# MON-PCP-2-2.net
KiCad netlist of a schematic drawn in EAGLE
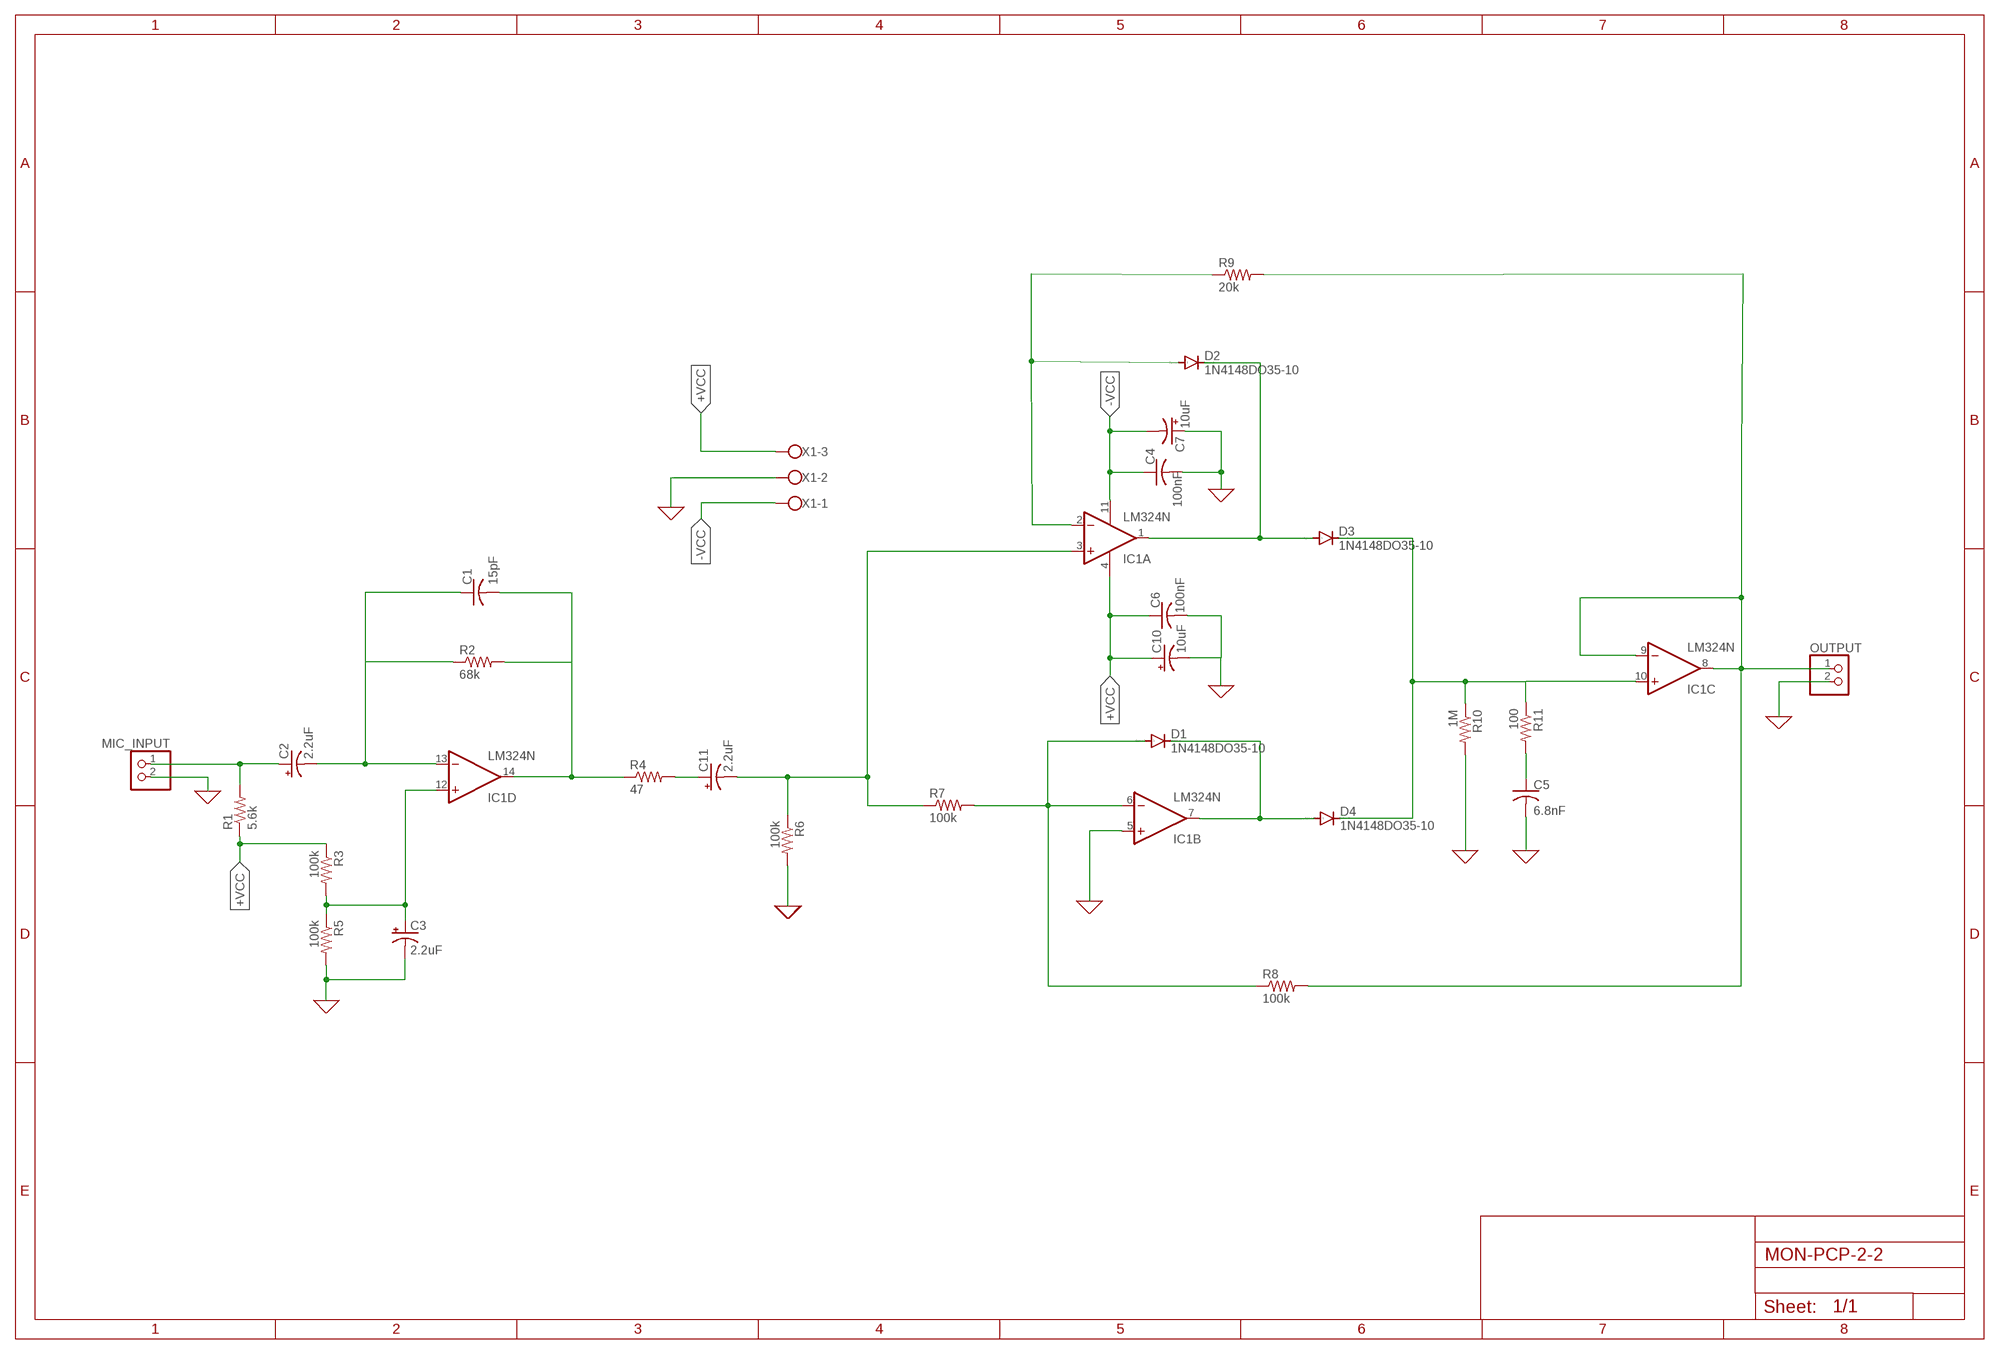
[diagram p0: schematic, sheet 1]

(export (version "E")
  (design (tool "Eeschema 10.0.6"))
  (components
    (comp (ref "C1")
      (value "15pF")
      (footprint "eagle-import:C050-025X075")
      (libsource (lib "eagle-import") (part "C-US050-025X075"))
    )
    (comp (ref "C2")
      (value "2.2uF")
      (footprint "eagle-import:E2,5-7")
      (libsource (lib "eagle-import") (part "CPOL-USE2.5-7"))
    )
    (comp (ref "C3")
      (value "2.2uF")
      (footprint "eagle-import:E2,5-7")
      (libsource (lib "eagle-import") (part "CPOL-USE2.5-7"))
    )
    (comp (ref "C4")
      (value "100nF")
      (footprint "eagle-import:C050-025X075")
      (libsource (lib "eagle-import") (part "C-US050-025X075"))
    )
    (comp (ref "C5")
      (value "6.8nF")
      (footprint "eagle-import:C050-025X075")
      (libsource (lib "eagle-import") (part "C-US050-025X075"))
    )
    (comp (ref "C6")
      (value "100nF")
      (footprint "eagle-import:C050-025X075")
      (libsource (lib "eagle-import") (part "C-US050-025X075"))
    )
    (comp (ref "C7")
      (value "10uF")
      (footprint "eagle-import:E2,5-7")
      (libsource (lib "eagle-import") (part "CPOL-USE2.5-7"))
    )
    (comp (ref "C10")
      (value "10uF")
      (footprint "eagle-import:E2,5-7")
      (libsource (lib "eagle-import") (part "CPOL-USE2.5-7"))
    )
    (comp (ref "C11")
      (value "2.2uF")
      (footprint "eagle-import:E2,5-7")
      (libsource (lib "eagle-import") (part "CPOL-USE2.5-7"))
    )
    (comp (ref "D1")
      (value "1N4148DO35-10")
      (footprint "eagle-import:DO35-10")
      (libsource (lib "eagle-import") (part "1N4148DO35-10"))
    )
    (comp (ref "D2")
      (value "1N4148DO35-10")
      (footprint "eagle-import:DO35-10")
      (libsource (lib "eagle-import") (part "1N4148DO35-10"))
    )
    (comp (ref "D3")
      (value "1N4148DO35-10")
      (footprint "eagle-import:DO35-10")
      (libsource (lib "eagle-import") (part "1N4148DO35-10"))
    )
    (comp (ref "D4")
      (value "1N4148DO35-10")
      (footprint "eagle-import:DO35-10")
      (libsource (lib "eagle-import") (part "1N4148DO35-10"))
    )
    (comp (ref "IC1")
      (value "LM324N")
      (footprint "eagle-import:DIL14")
      (libsource (lib "eagle-import") (part "LM324N"))
    )
    (comp (ref "MIC_INPUT")
      (value "PINHD-1X2")
      (footprint "eagle-import:1X02")
      (libsource (lib "eagle-import") (part "PINHD-1X2"))
    )
    (comp (ref "OUTPUT")
      (value "PINHD-1X2")
      (footprint "eagle-import:1X02")
      (libsource (lib "eagle-import") (part "PINHD-1X2"))
    )
    (comp (ref "R1")
      (value "5.6k")
      (footprint "eagle-import:0207_10")
      (libsource (lib "eagle-import") (part "R-US_0207/10"))
    )
    (comp (ref "R2")
      (value "68k")
      (footprint "eagle-import:0207_10")
      (libsource (lib "eagle-import") (part "R-US_0207/10"))
    )
    (comp (ref "R3")
      (value "100k")
      (footprint "eagle-import:0207_10")
      (libsource (lib "eagle-import") (part "R-US_0207/10"))
    )
    (comp (ref "R4")
      (value "47")
      (footprint "eagle-import:0207_10")
      (libsource (lib "eagle-import") (part "R-US_0207/10"))
    )
    (comp (ref "R5")
      (value "100k")
      (footprint "eagle-import:0207_10")
      (libsource (lib "eagle-import") (part "R-US_0207/10"))
    )
    (comp (ref "R6")
      (value "100k")
      (footprint "eagle-import:0207_10")
      (libsource (lib "eagle-import") (part "R-US_0207/10"))
    )
    (comp (ref "R7")
      (value "100k")
      (footprint "eagle-import:0207_10")
      (libsource (lib "eagle-import") (part "R-US_0207/10"))
    )
    (comp (ref "R8")
      (value "100k")
      (footprint "eagle-import:0207_10")
      (libsource (lib "eagle-import") (part "R-US_0207/10"))
    )
    (comp (ref "R9")
      (value "20k")
      (footprint "eagle-import:0207_10")
      (libsource (lib "eagle-import") (part "R-US_0207/10"))
    )
    (comp (ref "R10")
      (value "1M")
      (footprint "eagle-import:0207_10")
      (libsource (lib "eagle-import") (part "R-US_0207/10"))
    )
    (comp (ref "R11")
      (value "100")
      (footprint "eagle-import:0207_10")
      (libsource (lib "eagle-import") (part "R-US_0207/10"))
    )
    (comp (ref "X1")
      (value "W237-103")
      (footprint "eagle-import:W237-103")
      (fields (field (name "MPN") "237-103"))
      (libsource (lib "eagle-import") (part "W237-103"))
    )
  )
  (nets
    (net (code "1") (name "+VCC") (class "Default")
      (node (ref "C10") (pin "+") (pinfunction "+_+") (pintype "passive"))
      (node (ref "C6") (pin "1") (pinfunction "1_1") (pintype "passive"))
      (node (ref "IC1") (pin "4") (pinfunction "V+_4") (pintype "power_in"))
      (node (ref "R1") (pin "1") (pinfunction "1_1") (pintype "passive"))
      (node (ref "R3") (pin "1") (pinfunction "1_1") (pintype "passive"))
      (node (ref "X1") (pin "3") (pinfunction "KL_3") (pintype "passive"))
    )
    (net (code "2") (name "-VCC") (class "Default")
      (node (ref "C4") (pin "1") (pinfunction "1_1") (pintype "passive"))
      (node (ref "C7") (pin "-") (pinfunction "-_-") (pintype "passive"))
      (node (ref "IC1") (pin "11") (pinfunction "V-_11") (pintype "power_in"))
      (node (ref "X1") (pin "1") (pinfunction "KL_1") (pintype "passive"))
    )
    (net (code "3") (name "GND") (class "Default")
      (node (ref "C10") (pin "-") (pinfunction "-_-") (pintype "passive"))
      (node (ref "C3") (pin "-") (pinfunction "-_-") (pintype "passive"))
      (node (ref "C4") (pin "2") (pinfunction "2_2") (pintype "passive"))
      (node (ref "C5") (pin "2") (pinfunction "2_2") (pintype "passive"))
      (node (ref "C6") (pin "2") (pinfunction "2_2") (pintype "passive"))
      (node (ref "C7") (pin "+") (pinfunction "+_+") (pintype "passive"))
      (node (ref "IC1") (pin "5") (pinfunction "+IN_5") (pintype "input"))
      (node (ref "MIC_INPUT") (pin "2") (pinfunction "2_2") (pintype "passive"))
      (node (ref "OUTPUT") (pin "2") (pinfunction "2_2") (pintype "passive"))
      (node (ref "R10") (pin "2") (pinfunction "2_2") (pintype "passive"))
      (node (ref "R5") (pin "2") (pinfunction "2_2") (pintype "passive"))
      (node (ref "R6") (pin "2") (pinfunction "2_2") (pintype "passive"))
      (node (ref "X1") (pin "2") (pinfunction "KL_2") (pintype "passive"))
    )
    (net (code "4") (name "Net-(C2-Pad+)") (class "Default")
      (node (ref "C2") (pin "+") (pinfunction "+_+") (pintype "passive"))
      (node (ref "MIC_INPUT") (pin "1") (pinfunction "1_1") (pintype "passive"))
      (node (ref "R1") (pin "2") (pinfunction "2_2") (pintype "passive"))
    )
    (net (code "5") (name "Net-(C5-Pad1)") (class "Default")
      (node (ref "C5") (pin "1") (pinfunction "1_1") (pintype "passive"))
      (node (ref "R11") (pin "2") (pinfunction "2_2") (pintype "passive"))
    )
    (net (code "6") (name "Net-(C11-Pad+)") (class "Default")
      (node (ref "C11") (pin "+") (pinfunction "+_+") (pintype "passive"))
      (node (ref "R4") (pin "2") (pinfunction "2_2") (pintype "passive"))
    )
    (net (code "7") (name "Net-(IC1A-+IN)") (class "Default")
      (node (ref "C11") (pin "-") (pinfunction "-_-") (pintype "passive"))
      (node (ref "IC1") (pin "3") (pinfunction "+IN_3") (pintype "input"))
      (node (ref "R6") (pin "1") (pinfunction "1_1") (pintype "passive"))
      (node (ref "R7") (pin "1") (pinfunction "1_1") (pintype "passive"))
    )
    (net (code "8") (name "Net-(IC1A--IN)") (class "Default")
      (node (ref "D2") (pin "A") (pinfunction "A_A") (pintype "passive"))
      (node (ref "IC1") (pin "2") (pinfunction "-IN_2") (pintype "input"))
      (node (ref "R9") (pin "1") (pinfunction "1_1") (pintype "passive"))
    )
    (net (code "9") (name "Net-(IC1A-OUT)") (class "Default")
      (node (ref "D2") (pin "C") (pinfunction "C_C") (pintype "passive"))
      (node (ref "D3") (pin "A") (pinfunction "A_A") (pintype "passive"))
      (node (ref "IC1") (pin "1") (pinfunction "OUT_1") (pintype "output"))
    )
    (net (code "10") (name "Net-(IC1B--IN)") (class "Default")
      (node (ref "D1") (pin "A") (pinfunction "A_A") (pintype "passive"))
      (node (ref "IC1") (pin "6") (pinfunction "-IN_6") (pintype "input"))
      (node (ref "R7") (pin "2") (pinfunction "2_2") (pintype "passive"))
      (node (ref "R8") (pin "1") (pinfunction "1_1") (pintype "passive"))
    )
    (net (code "11") (name "Net-(IC1B-OUT)") (class "Default")
      (node (ref "D1") (pin "C") (pinfunction "C_C") (pintype "passive"))
      (node (ref "D4") (pin "A") (pinfunction "A_A") (pintype "passive"))
      (node (ref "IC1") (pin "7") (pinfunction "OUT_7") (pintype "output"))
    )
    (net (code "12") (name "Net-(IC1C-+IN)") (class "Default")
      (node (ref "D3") (pin "C") (pinfunction "C_C") (pintype "passive"))
      (node (ref "D4") (pin "C") (pinfunction "C_C") (pintype "passive"))
      (node (ref "IC1") (pin "10") (pinfunction "+IN_10") (pintype "input"))
      (node (ref "R10") (pin "1") (pinfunction "1_1") (pintype "passive"))
      (node (ref "R11") (pin "1") (pinfunction "1_1") (pintype "passive"))
    )
    (net (code "13") (name "Net-(IC1C--IN)") (class "Default")
      (node (ref "IC1") (pin "8") (pinfunction "OUT_8") (pintype "output"))
      (node (ref "IC1") (pin "9") (pinfunction "-IN_9") (pintype "input"))
      (node (ref "OUTPUT") (pin "1") (pinfunction "1_1") (pintype "passive"))
      (node (ref "R8") (pin "2") (pinfunction "2_2") (pintype "passive"))
      (node (ref "R9") (pin "2") (pinfunction "2_2") (pintype "passive"))
    )
    (net (code "14") (name "Net-(IC1D-+IN)") (class "Default")
      (node (ref "C3") (pin "+") (pinfunction "+_+") (pintype "passive"))
      (node (ref "IC1") (pin "12") (pinfunction "+IN_12") (pintype "input"))
      (node (ref "R3") (pin "2") (pinfunction "2_2") (pintype "passive"))
      (node (ref "R5") (pin "1") (pinfunction "1_1") (pintype "passive"))
    )
    (net (code "15") (name "Net-(IC1D--IN)") (class "Default")
      (node (ref "C1") (pin "1") (pinfunction "1_1") (pintype "passive"))
      (node (ref "C2") (pin "-") (pinfunction "-_-") (pintype "passive"))
      (node (ref "IC1") (pin "13") (pinfunction "-IN_13") (pintype "input"))
      (node (ref "R2") (pin "1") (pinfunction "1_1") (pintype "passive"))
    )
    (net (code "16") (name "Net-(IC1D-OUT)") (class "Default")
      (node (ref "C1") (pin "2") (pinfunction "2_2") (pintype "passive"))
      (node (ref "IC1") (pin "14") (pinfunction "OUT_14") (pintype "output"))
      (node (ref "R2") (pin "2") (pinfunction "2_2") (pintype "passive"))
      (node (ref "R4") (pin "1") (pinfunction "1_1") (pintype "passive"))
    )
  )
)
